# DSPPower.net
KiCad netlist of a schematic drawn in Altium Designer
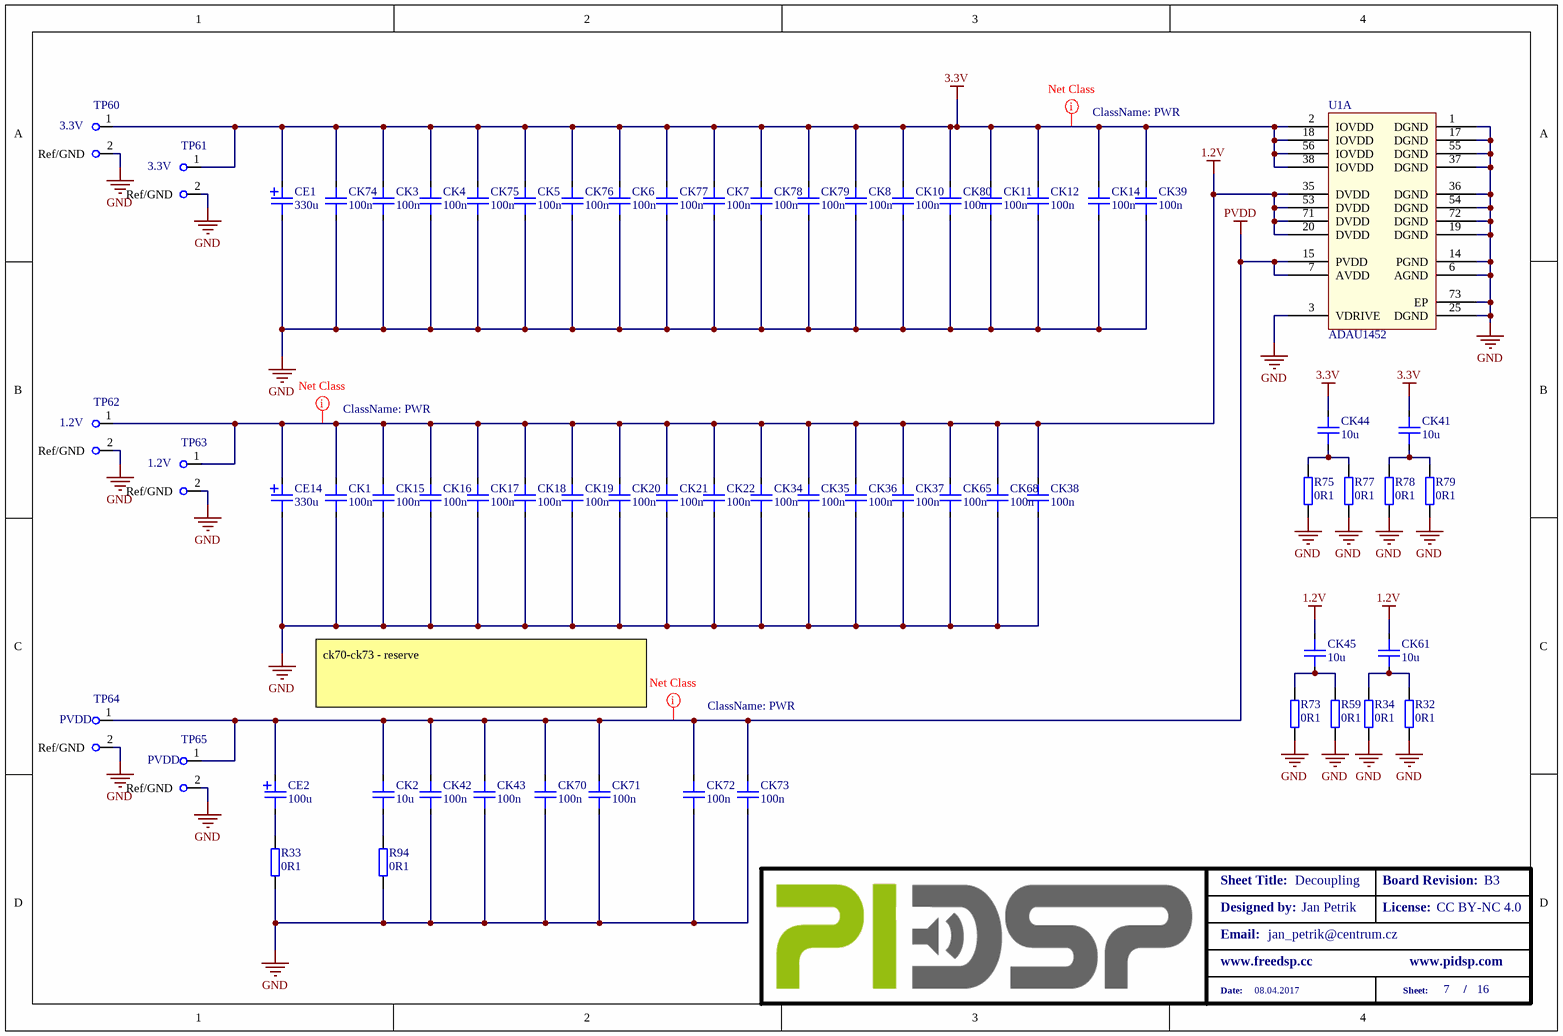
[diagram p0: DSPPower.SchDoc]

(export (version "E")
  (design (tool "Eeschema 10.0.6"))
  (components
    (comp (ref "CE1")
      (value "330u")
      (footprint "CAPAE6.8X6.8(D_SIZE)")
      (description "Polymer Aluminium Solid Capacitor 330uF, 6.3V")
      (fields
        (field (name "VOLTAGE") "6.3V")
        (field (name "TOLERANCE") "20%/35V")
        (field (name "AUTHOR") "JP/27.03.2014")
      )
      (libsource (lib "JP_C") (part "330u-6.3V-B6-OSCON"))
    )
    (comp (ref "CE2")
      (value "100u")
      (footprint "CAPAE6.8X6.8(D_SIZE)")
      (description "Polymer Aluminium Solid Capacitor 100uF, 16V")
      (fields
        (field (name "TOLERANCE") "20%/16V")
        (field (name "VOLTAGE") "16V")
        (field (name "AUTHOR") "JP/27.03.2014")
      )
      (libsource (lib "JP_C") (part "100u-16V-B6-OSCON"))
    )
    (comp (ref "CE14")
      (value "330u")
      (footprint "CAPAE6.8X6.8(D_SIZE)")
      (description "Polymer Aluminium Solid Capacitor 330uF, 6.3V")
      (fields
        (field (name "VOLTAGE") "6.3V")
        (field (name "TOLERANCE") "20%/35V")
        (field (name "AUTHOR") "JP/27.03.2014")
      )
      (libsource (lib "JP_C") (part "330u-6.3V-B6-OSCON"))
    )
    (comp (ref "CK1")
      (value "100n")
      (footprint "CAPC1608X09N(SMC0603)")
      (description "MLCC")
      (fields
        (field (name "TOLERANCE") "10%")
        (field (name "VOLTAGE") "50V")
        (field (name "AUTHOR") "JP/27.03.2014")
      )
      (libsource (lib "JP_C") (part "100n-50V-0603-X7R"))
    )
    (comp (ref "CK2")
      (value "10u")
      (footprint "CAPC3216X12N(SMC1206)")
      (description "MLCC")
      (fields
        (field (name "TOLERANCE") "10%")
        (field (name "VOLTAGE") "50")
        (field (name "AUTHOR") "JP/10.06.2014")
      )
      (libsource (lib "JP_C") (part "10u-50V-1206-X5R"))
    )
    (comp (ref "CK3")
      (value "100n")
      (footprint "CAPC1608X09N(SMC0603)_Fanout")
      (description "MLCC")
      (fields
        (field (name "TOLERANCE") "10%")
        (field (name "VOLTAGE") "50V")
        (field (name "AUTHOR") "JP/27.03.2014")
      )
      (libsource (lib "JP_C") (part "100n-50V-0603-X7R"))
    )
    (comp (ref "CK4")
      (value "100n")
      (footprint "CAPC1608X09N(SMC0603)_Fanout")
      (description "MLCC")
      (fields
        (field (name "TOLERANCE") "10%")
        (field (name "VOLTAGE") "50V")
        (field (name "AUTHOR") "JP/27.03.2014")
      )
      (libsource (lib "JP_C") (part "100n-50V-0603-X7R"))
    )
    (comp (ref "CK5")
      (value "100n")
      (footprint "CAPC1608X09N(SMC0603)_Fanout")
      (description "MLCC")
      (fields
        (field (name "VOLTAGE") "50V")
        (field (name "TOLERANCE") "10%")
        (field (name "AUTHOR") "JP/27.03.2014")
      )
      (libsource (lib "JP_C") (part "100n-50V-0603-X7R"))
    )
    (comp (ref "CK6")
      (value "100n")
      (footprint "CAPC1608X09N(SMC0603)_Fanout")
      (description "MLCC")
      (fields
        (field (name "VOLTAGE") "50V")
        (field (name "TOLERANCE") "10%")
        (field (name "AUTHOR") "JP/27.03.2014")
      )
      (libsource (lib "JP_C") (part "100n-50V-0603-X7R"))
    )
    (comp (ref "CK7")
      (value "100n")
      (footprint "CAPC1608X09N(SMC0603)_Fanout")
      (description "MLCC")
      (fields
        (field (name "VOLTAGE") "50V")
        (field (name "TOLERANCE") "10%")
        (field (name "AUTHOR") "JP/27.03.2014")
      )
      (libsource (lib "JP_C") (part "100n-50V-0603-X7R"))
    )
    (comp (ref "CK8")
      (value "100n")
      (footprint "CAPC1608X09N(SMC0603)_Fanout")
      (description "MLCC")
      (fields
        (field (name "VOLTAGE") "50V")
        (field (name "TOLERANCE") "10%")
        (field (name "AUTHOR") "JP/27.03.2014")
      )
      (libsource (lib "JP_C") (part "100n-50V-0603-X7R"))
    )
    (comp (ref "CK10")
      (value "100n")
      (footprint "CAPC1608X09N(SMC0603)_Fanout")
      (description "MLCC")
      (fields
        (field (name "VOLTAGE") "50V")
        (field (name "TOLERANCE") "10%")
        (field (name "AUTHOR") "JP/27.03.2014")
      )
      (libsource (lib "JP_C") (part "100n-50V-0603-X7R"))
    )
    (comp (ref "CK11")
      (value "100n")
      (footprint "CAPC1608X09N(SMC0603)")
      (description "MLCC")
      (fields
        (field (name "VOLTAGE") "50V")
        (field (name "TOLERANCE") "10%")
        (field (name "AUTHOR") "JP/27.03.2014")
      )
      (libsource (lib "JP_C") (part "100n-50V-0603-X7R"))
    )
    (comp (ref "CK12")
      (value "100n")
      (footprint "CAPC1608X09N(SMC0603)")
      (description "MLCC")
      (fields
        (field (name "VOLTAGE") "50V")
        (field (name "TOLERANCE") "10%")
        (field (name "AUTHOR") "JP/27.03.2014")
      )
      (libsource (lib "JP_C") (part "100n-50V-0603-X7R"))
    )
    (comp (ref "CK14")
      (value "100n")
      (footprint "CAPC1608X09N(SMC0603)")
      (description "MLCC")
      (fields
        (field (name "VOLTAGE") "50V")
        (field (name "TOLERANCE") "10%")
        (field (name "AUTHOR") "JP/27.03.2014")
      )
      (libsource (lib "JP_C") (part "100n-50V-0603-X7R"))
    )
    (comp (ref "CK15")
      (value "100n")
      (footprint "CAPC1608X09N(SMC0603)")
      (description "MLCC")
      (fields
        (field (name "TOLERANCE") "10%")
        (field (name "VOLTAGE") "50V")
        (field (name "AUTHOR") "JP/27.03.2014")
      )
      (libsource (lib "JP_C") (part "100n-50V-0603-X7R"))
    )
    (comp (ref "CK16")
      (value "100n")
      (footprint "CAPC1608X09N(SMC0603)")
      (description "MLCC")
      (fields
        (field (name "TOLERANCE") "10%")
        (field (name "VOLTAGE") "50V")
        (field (name "AUTHOR") "JP/27.03.2014")
      )
      (libsource (lib "JP_C") (part "100n-50V-0603-X7R"))
    )
    (comp (ref "CK17")
      (value "100n")
      (footprint "CAPC1608X09N(SMC0603)")
      (description "MLCC")
      (fields
        (field (name "VOLTAGE") "50V")
        (field (name "TOLERANCE") "10%")
        (field (name "AUTHOR") "JP/27.03.2014")
      )
      (libsource (lib "JP_C") (part "100n-50V-0603-X7R"))
    )
    (comp (ref "CK18")
      (value "100n")
      (footprint "CAPC1608X09N(SMC0603)")
      (description "MLCC")
      (fields
        (field (name "VOLTAGE") "50V")
        (field (name "TOLERANCE") "10%")
        (field (name "AUTHOR") "JP/27.03.2014")
      )
      (libsource (lib "JP_C") (part "100n-50V-0603-X7R"))
    )
    (comp (ref "CK19")
      (value "100n")
      (footprint "CAPC1608X09N(SMC0603)")
      (description "MLCC")
      (fields
        (field (name "VOLTAGE") "50V")
        (field (name "TOLERANCE") "10%")
        (field (name "AUTHOR") "JP/27.03.2014")
      )
      (libsource (lib "JP_C") (part "100n-50V-0603-X7R"))
    )
    (comp (ref "CK20")
      (value "100n")
      (footprint "CAPC1608X09N(SMC0603)")
      (description "MLCC")
      (fields
        (field (name "VOLTAGE") "50V")
        (field (name "TOLERANCE") "10%")
        (field (name "AUTHOR") "JP/27.03.2014")
      )
      (libsource (lib "JP_C") (part "100n-50V-0603-X7R"))
    )
    (comp (ref "CK21")
      (value "100n")
      (footprint "CAPC1608X09N(SMC0603)")
      (description "MLCC")
      (fields
        (field (name "VOLTAGE") "50V")
        (field (name "TOLERANCE") "10%")
        (field (name "AUTHOR") "JP/27.03.2014")
      )
      (libsource (lib "JP_C") (part "100n-50V-0603-X7R"))
    )
    (comp (ref "CK22")
      (value "100n")
      (footprint "CAPC1608X09N(SMC0603)")
      (description "MLCC")
      (fields
        (field (name "TOLERANCE") "10%")
        (field (name "VOLTAGE") "50V")
        (field (name "AUTHOR") "JP/27.03.2014")
      )
      (libsource (lib "JP_C") (part "100n-50V-0603-X7R"))
    )
    (comp (ref "CK34")
      (value "100n")
      (footprint "CAPC1608X09N(SMC0603)")
      (description "MLCC")
      (fields
        (field (name "TOLERANCE") "10%")
        (field (name "VOLTAGE") "50V")
        (field (name "AUTHOR") "JP/27.03.2014")
      )
      (libsource (lib "JP_C") (part "100n-50V-0603-X7R"))
    )
    (comp (ref "CK35")
      (value "100n")
      (footprint "CAPC1608X09N(SMC0603)")
      (description "MLCC")
      (fields
        (field (name "TOLERANCE") "10%")
        (field (name "VOLTAGE") "50V")
        (field (name "AUTHOR") "JP/27.03.2014")
      )
      (libsource (lib "JP_C") (part "100n-50V-0603-X7R"))
    )
    (comp (ref "CK36")
      (value "100n")
      (footprint "CAPC1608X09N(SMC0603)")
      (description "MLCC")
      (fields
        (field (name "TOLERANCE") "10%")
        (field (name "VOLTAGE") "50V")
        (field (name "AUTHOR") "JP/27.03.2014")
      )
      (libsource (lib "JP_C") (part "100n-50V-0603-X7R"))
    )
    (comp (ref "CK37")
      (value "100n")
      (footprint "CAPC1608X09N(SMC0603)")
      (description "MLCC")
      (fields
        (field (name "TOLERANCE") "10%")
        (field (name "VOLTAGE") "50V")
        (field (name "AUTHOR") "JP/27.03.2014")
      )
      (libsource (lib "JP_C") (part "100n-50V-0603-X7R"))
    )
    (comp (ref "CK38")
      (value "100n")
      (footprint "CAPC1608X09N(SMC0603)")
      (description "MLCC")
      (fields
        (field (name "TOLERANCE") "10%")
        (field (name "VOLTAGE") "50V")
        (field (name "AUTHOR") "JP/27.03.2014")
      )
      (libsource (lib "JP_C") (part "100n-50V-0603-X7R"))
    )
    (comp (ref "CK39")
      (value "100n")
      (footprint "CAPC1608X09N(SMC0603)")
      (description "MLCC")
      (fields
        (field (name "VOLTAGE") "50V")
        (field (name "TOLERANCE") "10%")
        (field (name "AUTHOR") "JP/27.03.2014")
      )
      (libsource (lib "JP_C") (part "100n-50V-0603-X7R"))
    )
    (comp (ref "CK41")
      (value "10u")
      (footprint "CAPC3216X12N(SMC1206)")
      (description "MLCC")
      (fields
        (field (name "TOLERANCE") "10%")
        (field (name "VOLTAGE") "50")
        (field (name "AUTHOR") "JP/10.06.2014")
      )
      (libsource (lib "JP_C") (part "10u-50V-1206-X5R"))
    )
    (comp (ref "CK42")
      (value "100n")
      (footprint "CAPC1608X09N(SMC0603)")
      (description "MLCC")
      (fields
        (field (name "TOLERANCE") "10%")
        (field (name "VOLTAGE") "50V")
        (field (name "AUTHOR") "JP/27.03.2014")
      )
      (libsource (lib "JP_C") (part "100n-50V-0603-X7R"))
    )
    (comp (ref "CK43")
      (value "100n")
      (footprint "CAPC1608X09N(SMC0603)")
      (description "MLCC")
      (fields
        (field (name "VOLTAGE") "50V")
        (field (name "TOLERANCE") "10%")
        (field (name "AUTHOR") "JP/27.03.2014")
      )
      (libsource (lib "JP_C") (part "100n-50V-0603-X7R"))
    )
    (comp (ref "CK44")
      (value "10u")
      (footprint "CAPC3216X12N(SMC1206)")
      (description "MLCC")
      (fields
        (field (name "TOLERANCE") "10%")
        (field (name "VOLTAGE") "50")
        (field (name "AUTHOR") "JP/10.06.2014")
      )
      (libsource (lib "JP_C") (part "10u-50V-1206-X5R"))
    )
    (comp (ref "CK45")
      (value "10u")
      (footprint "CAPC3216X12N(SMC1206)")
      (description "MLCC")
      (fields
        (field (name "TOLERANCE") "10%")
        (field (name "VOLTAGE") "50")
        (field (name "AUTHOR") "JP/10.06.2014")
      )
      (libsource (lib "JP_C") (part "10u-50V-1206-X5R"))
    )
    (comp (ref "CK61")
      (value "10u")
      (footprint "CAPC3216X12N(SMC1206)")
      (description "MLCC")
      (fields
        (field (name "TOLERANCE") "10%")
        (field (name "VOLTAGE") "50")
        (field (name "AUTHOR") "JP/10.06.2014")
      )
      (libsource (lib "JP_C") (part "10u-50V-1206-X5R"))
    )
    (comp (ref "CK65")
      (value "100n")
      (footprint "CAPC1608X09N(SMC0603)")
      (description "MLCC")
      (fields
        (field (name "TOLERANCE") "10%")
        (field (name "VOLTAGE") "50V")
        (field (name "AUTHOR") "JP/27.03.2014")
      )
      (libsource (lib "JP_C") (part "100n-50V-0603-X7R"))
    )
    (comp (ref "CK68")
      (value "100n")
      (footprint "CAPC1608X09N(SMC0603)")
      (description "MLCC")
      (fields
        (field (name "TOLERANCE") "10%")
        (field (name "VOLTAGE") "50V")
        (field (name "AUTHOR") "JP/27.03.2014")
      )
      (libsource (lib "JP_C") (part "100n-50V-0603-X7R"))
    )
    (comp (ref "CK70")
      (value "100n")
      (footprint "CAPC1608X09N(SMC0603)")
      (description "MLCC")
      (fields
        (field (name "VOLTAGE") "50V")
        (field (name "TOLERANCE") "10%")
        (field (name "AUTHOR") "JP/27.03.2014")
      )
      (libsource (lib "JP_C") (part "100n-50V-0603-X7R"))
    )
    (comp (ref "CK71")
      (value "100n")
      (footprint "CAPC1608X09N(SMC0603)")
      (description "MLCC")
      (fields
        (field (name "VOLTAGE") "50V")
        (field (name "TOLERANCE") "10%")
        (field (name "AUTHOR") "JP/27.03.2014")
      )
      (libsource (lib "JP_C") (part "100n-50V-0603-X7R"))
    )
    (comp (ref "CK72")
      (value "100n")
      (footprint "CAPC1608X09N(SMC0603)")
      (description "MLCC")
      (fields
        (field (name "VOLTAGE") "50V")
        (field (name "TOLERANCE") "10%")
        (field (name "AUTHOR") "JP/27.03.2014")
      )
      (libsource (lib "JP_C") (part "100n-50V-0603-X7R"))
    )
    (comp (ref "CK73")
      (value "100n")
      (footprint "CAPC1608X09N(SMC0603)")
      (description "MLCC")
      (fields
        (field (name "VOLTAGE") "50V")
        (field (name "TOLERANCE") "10%")
        (field (name "AUTHOR") "JP/27.03.2014")
      )
      (libsource (lib "JP_C") (part "100n-50V-0603-X7R"))
    )
    (comp (ref "CK74")
      (value "100n")
      (footprint "CAPC1608X09N(SMC0603)_Fanout")
      (description "MLCC")
      (fields
        (field (name "VOLTAGE") "50V")
        (field (name "TOLERANCE") "10%")
        (field (name "AUTHOR") "JP/27.03.2014")
      )
      (libsource (lib "JP_C") (part "100n-50V-0603-X7R"))
    )
    (comp (ref "CK75")
      (value "100n")
      (footprint "CAPC1608X09N(SMC0603)_Fanout")
      (description "MLCC")
      (fields
        (field (name "VOLTAGE") "50V")
        (field (name "TOLERANCE") "10%")
        (field (name "AUTHOR") "JP/27.03.2014")
      )
      (libsource (lib "JP_C") (part "100n-50V-0603-X7R"))
    )
    (comp (ref "CK76")
      (value "100n")
      (footprint "CAPC1608X09N(SMC0603)_Fanout")
      (description "MLCC")
      (fields
        (field (name "VOLTAGE") "50V")
        (field (name "TOLERANCE") "10%")
        (field (name "AUTHOR") "JP/27.03.2014")
      )
      (libsource (lib "JP_C") (part "100n-50V-0603-X7R"))
    )
    (comp (ref "CK77")
      (value "100n")
      (footprint "CAPC1608X09N(SMC0603)_Fanout")
      (description "MLCC")
      (fields
        (field (name "VOLTAGE") "50V")
        (field (name "TOLERANCE") "10%")
        (field (name "AUTHOR") "JP/27.03.2014")
      )
      (libsource (lib "JP_C") (part "100n-50V-0603-X7R"))
    )
    (comp (ref "CK78")
      (value "100n")
      (footprint "CAPC1608X09N(SMC0603)_Fanout")
      (description "MLCC")
      (fields
        (field (name "VOLTAGE") "50V")
        (field (name "TOLERANCE") "10%")
        (field (name "AUTHOR") "JP/27.03.2014")
      )
      (libsource (lib "JP_C") (part "100n-50V-0603-X7R"))
    )
    (comp (ref "CK79")
      (value "100n")
      (footprint "CAPC1608X09N(SMC0603)_Fanout")
      (description "MLCC")
      (fields
        (field (name "VOLTAGE") "50V")
        (field (name "TOLERANCE") "10%")
        (field (name "AUTHOR") "JP/27.03.2014")
      )
      (libsource (lib "JP_C") (part "100n-50V-0603-X7R"))
    )
    (comp (ref "CK80")
      (value "100n")
      (footprint "CAPC1608X09N(SMC0603)_Fanout")
      (description "MLCC")
      (fields
        (field (name "VOLTAGE") "50V")
        (field (name "TOLERANCE") "10%")
        (field (name "AUTHOR") "JP/27.03.2014")
      )
      (libsource (lib "JP_C") (part "100n-50V-0603-X7R"))
    )
    (comp (ref "R32")
      (value "0R1")
      (footprint "RESC1608X06N(SMR0603)")
      (description "Chip Resistor")
      (fields (field (name "AUTHOR") "JP/10.06.2014"))
      (libsource (lib "JP_R") (part "0R1-100mW-0603-ThickFilm"))
    )
    (comp (ref "R33")
      (value "0R1")
      (footprint "RESC1608X06N(SMR0603)")
      (description "Chip Resistor")
      (fields (field (name "AUTHOR") "JP/10.06.2014"))
      (libsource (lib "JP_R") (part "0R1-100mW-0603-ThickFilm"))
    )
    (comp (ref "R34")
      (value "0R1")
      (footprint "RESC1608X06N(SMR0603)")
      (description "Chip Resistor")
      (fields (field (name "AUTHOR") "JP/10.06.2014"))
      (libsource (lib "JP_R") (part "0R1-100mW-0603-ThickFilm"))
    )
    (comp (ref "R59")
      (value "0R1")
      (footprint "RESC1608X06N(SMR0603)")
      (description "Chip Resistor")
      (fields (field (name "AUTHOR") "JP/10.06.2014"))
      (libsource (lib "JP_R") (part "0R1-100mW-0603-ThickFilm"))
    )
    (comp (ref "R73")
      (value "0R1")
      (footprint "RESC1608X06N(SMR0603)")
      (description "Chip Resistor")
      (fields (field (name "AUTHOR") "JP/10.06.2014"))
      (libsource (lib "JP_R") (part "0R1-100mW-0603-ThickFilm"))
    )
    (comp (ref "R75")
      (value "0R1")
      (footprint "RESC1608X06N(SMR0603)")
      (description "Chip Resistor")
      (fields (field (name "AUTHOR") "JP/10.06.2014"))
      (libsource (lib "JP_R") (part "0R1-100mW-0603-ThickFilm"))
    )
    (comp (ref "R77")
      (value "0R1")
      (footprint "RESC1608X06N(SMR0603)")
      (description "Chip Resistor")
      (fields (field (name "AUTHOR") "JP/10.06.2014"))
      (libsource (lib "JP_R") (part "0R1-100mW-0603-ThickFilm"))
    )
    (comp (ref "R78")
      (value "0R1")
      (footprint "RESC1608X06N(SMR0603)")
      (description "Chip Resistor")
      (fields (field (name "AUTHOR") "JP/10.06.2014"))
      (libsource (lib "JP_R") (part "0R1-100mW-0603-ThickFilm"))
    )
    (comp (ref "R79")
      (value "0R1")
      (footprint "RESC1608X06N(SMR0603)")
      (description "Chip Resistor")
      (fields (field (name "AUTHOR") "JP/10.06.2014"))
      (libsource (lib "JP_R") (part "0R1-100mW-0603-ThickFilm"))
    )
    (comp (ref "R94")
      (value "0R1")
      (footprint "RESC1608X06N(SMR0603)")
      (description "Chip Resistor")
      (fields (field (name "AUTHOR") "JP/10.06.2014"))
      (libsource (lib "JP_R") (part "0R1-100mW-0603-ThickFilm"))
    )
    (comp (ref "TP60")
      (value "3.3V")
      (footprint "JP_Misc:HS/PDN_Testpoint")
      (description "Testpoint - HS/PDN")
      (libsource (lib "JP_Misc") (part "TEST_POINT_HS/PDN"))
    )
    (comp (ref "TP61")
      (value "3.3V")
      (footprint "JP_Misc:HS/PDN_Testpoint")
      (description "Testpoint - HS/PDN")
      (libsource (lib "JP_Misc") (part "TEST_POINT_HS/PDN"))
    )
    (comp (ref "TP62")
      (value "1.2V")
      (footprint "JP_Misc:HS/PDN_Testpoint")
      (description "Testpoint - HS/PDN")
      (libsource (lib "JP_Misc") (part "TEST_POINT_HS/PDN"))
    )
    (comp (ref "TP63")
      (value "1.2V")
      (footprint "JP_Misc:HS/PDN_Testpoint")
      (description "Testpoint - HS/PDN")
      (libsource (lib "JP_Misc") (part "TEST_POINT_HS/PDN"))
    )
    (comp (ref "TP64")
      (value "PVDD")
      (footprint "JP_Misc:HS/PDN_Testpoint")
      (description "Testpoint - HS/PDN")
      (libsource (lib "JP_Misc") (part "TEST_POINT_HS/PDN"))
    )
    (comp (ref "TP65")
      (value "PVDD")
      (footprint "JP_Misc:HS/PDN_Testpoint")
      (description "Testpoint - HS/PDN")
      (libsource (lib "JP_Misc") (part "TEST_POINT_HS/PDN"))
    )
    (comp (ref "U1")
      (value "ADAU1452")
      (footprint "CP_72_6-handsoldering")
      (libsource (lib "JP_IC") (part "ADAU1452"))
    )
  )
  (nets
    (net (code "1") (name "1.2V") (class "Default")
      (node (ref "CE14") (pin "1") (pinfunction "1_1") (pintype "passive"))
      (node (ref "CK1") (pin "1") (pinfunction "1_1") (pintype "passive"))
      (node (ref "CK15") (pin "1") (pinfunction "1_1") (pintype "passive"))
      (node (ref "CK16") (pin "1") (pinfunction "1_1") (pintype "passive"))
      (node (ref "CK17") (pin "1") (pinfunction "1_1") (pintype "passive"))
      (node (ref "CK18") (pin "1") (pinfunction "1_1") (pintype "passive"))
      (node (ref "CK19") (pin "1") (pinfunction "1_1") (pintype "passive"))
      (node (ref "CK20") (pin "1") (pinfunction "1_1") (pintype "passive"))
      (node (ref "CK21") (pin "1") (pinfunction "1_1") (pintype "passive"))
      (node (ref "CK22") (pin "1") (pinfunction "1_1") (pintype "passive"))
      (node (ref "CK34") (pin "1") (pinfunction "1_1") (pintype "passive"))
      (node (ref "CK35") (pin "1") (pinfunction "1_1") (pintype "passive"))
      (node (ref "CK36") (pin "1") (pinfunction "1_1") (pintype "passive"))
      (node (ref "CK37") (pin "1") (pinfunction "1_1") (pintype "passive"))
      (node (ref "CK38") (pin "1") (pinfunction "1_1") (pintype "passive"))
      (node (ref "CK45") (pin "1") (pinfunction "1_1") (pintype "passive"))
      (node (ref "CK61") (pin "1") (pinfunction "1_1") (pintype "passive"))
      (node (ref "CK65") (pin "1") (pinfunction "1_1") (pintype "passive"))
      (node (ref "CK68") (pin "1") (pinfunction "1_1") (pintype "passive"))
      (node (ref "TP62") (pin "1") (pintype "passive"))
      (node (ref "TP63") (pin "1") (pintype "passive"))
      (node (ref "U1") (pin "20") (pinfunction "DVDD_20") (pintype "power_in"))
      (node (ref "U1") (pin "35") (pinfunction "DVDD_35") (pintype "power_in"))
      (node (ref "U1") (pin "53") (pinfunction "DVDD_53") (pintype "power_in"))
      (node (ref "U1") (pin "71") (pinfunction "DVDD_71") (pintype "power_in"))
    )
    (net (code "2") (name "3.3V") (class "Default")
      (node (ref "CE1") (pin "1") (pinfunction "1_1") (pintype "passive"))
      (node (ref "CK10") (pin "1") (pinfunction "1_1") (pintype "passive"))
      (node (ref "CK11") (pin "1") (pinfunction "1_1") (pintype "passive"))
      (node (ref "CK12") (pin "1") (pinfunction "1_1") (pintype "passive"))
      (node (ref "CK14") (pin "1") (pinfunction "1_1") (pintype "passive"))
      (node (ref "CK3") (pin "1") (pinfunction "1_1") (pintype "passive"))
      (node (ref "CK39") (pin "1") (pinfunction "1_1") (pintype "passive"))
      (node (ref "CK4") (pin "1") (pinfunction "1_1") (pintype "passive"))
      (node (ref "CK41") (pin "1") (pinfunction "1_1") (pintype "passive"))
      (node (ref "CK44") (pin "1") (pinfunction "1_1") (pintype "passive"))
      (node (ref "CK5") (pin "1") (pinfunction "1_1") (pintype "passive"))
      (node (ref "CK6") (pin "1") (pinfunction "1_1") (pintype "passive"))
      (node (ref "CK7") (pin "1") (pinfunction "1_1") (pintype "passive"))
      (node (ref "CK74") (pin "1") (pinfunction "1_1") (pintype "passive"))
      (node (ref "CK75") (pin "1") (pinfunction "1_1") (pintype "passive"))
      (node (ref "CK76") (pin "1") (pinfunction "1_1") (pintype "passive"))
      (node (ref "CK77") (pin "1") (pinfunction "1_1") (pintype "passive"))
      (node (ref "CK78") (pin "1") (pinfunction "1_1") (pintype "passive"))
      (node (ref "CK79") (pin "1") (pinfunction "1_1") (pintype "passive"))
      (node (ref "CK8") (pin "1") (pinfunction "1_1") (pintype "passive"))
      (node (ref "CK80") (pin "1") (pinfunction "1_1") (pintype "passive"))
      (node (ref "TP60") (pin "1") (pintype "passive"))
      (node (ref "TP61") (pin "1") (pintype "passive"))
      (node (ref "U1") (pin "18") (pinfunction "IOVDD_18") (pintype "power_in"))
      (node (ref "U1") (pin "2") (pinfunction "IOVDD_2") (pintype "power_in"))
      (node (ref "U1") (pin "38") (pinfunction "IOVDD_38") (pintype "power_in"))
      (node (ref "U1") (pin "56") (pinfunction "IOVDD_56") (pintype "power_in"))
    )
    (net (code "3") (name "GND") (class "Default")
      (node (ref "CE1") (pin "2") (pinfunction "2_2") (pintype "passive"))
      (node (ref "CE14") (pin "2") (pinfunction "2_2") (pintype "passive"))
      (node (ref "CK1") (pin "2") (pinfunction "2_2") (pintype "passive"))
      (node (ref "CK10") (pin "2") (pinfunction "2_2") (pintype "passive"))
      (node (ref "CK11") (pin "2") (pinfunction "2_2") (pintype "passive"))
      (node (ref "CK12") (pin "2") (pinfunction "2_2") (pintype "passive"))
      (node (ref "CK14") (pin "2") (pinfunction "2_2") (pintype "passive"))
      (node (ref "CK15") (pin "2") (pinfunction "2_2") (pintype "passive"))
      (node (ref "CK16") (pin "2") (pinfunction "2_2") (pintype "passive"))
      (node (ref "CK17") (pin "2") (pinfunction "2_2") (pintype "passive"))
      (node (ref "CK18") (pin "2") (pinfunction "2_2") (pintype "passive"))
      (node (ref "CK19") (pin "2") (pinfunction "2_2") (pintype "passive"))
      (node (ref "CK20") (pin "2") (pinfunction "2_2") (pintype "passive"))
      (node (ref "CK21") (pin "2") (pinfunction "2_2") (pintype "passive"))
      (node (ref "CK22") (pin "2") (pinfunction "2_2") (pintype "passive"))
      (node (ref "CK3") (pin "2") (pinfunction "2_2") (pintype "passive"))
      (node (ref "CK34") (pin "2") (pinfunction "2_2") (pintype "passive"))
      (node (ref "CK35") (pin "2") (pinfunction "2_2") (pintype "passive"))
      (node (ref "CK36") (pin "2") (pinfunction "2_2") (pintype "passive"))
      (node (ref "CK37") (pin "2") (pinfunction "2_2") (pintype "passive"))
      (node (ref "CK38") (pin "2") (pinfunction "2_2") (pintype "passive"))
      (node (ref "CK39") (pin "2") (pinfunction "2_2") (pintype "passive"))
      (node (ref "CK4") (pin "2") (pinfunction "2_2") (pintype "passive"))
      (node (ref "CK42") (pin "2") (pinfunction "2_2") (pintype "passive"))
      (node (ref "CK43") (pin "2") (pinfunction "2_2") (pintype "passive"))
      (node (ref "CK5") (pin "2") (pinfunction "2_2") (pintype "passive"))
      (node (ref "CK6") (pin "2") (pinfunction "2_2") (pintype "passive"))
      (node (ref "CK65") (pin "2") (pinfunction "2_2") (pintype "passive"))
      (node (ref "CK68") (pin "2") (pinfunction "2_2") (pintype "passive"))
      (node (ref "CK7") (pin "2") (pinfunction "2_2") (pintype "passive"))
      (node (ref "CK70") (pin "2") (pinfunction "2_2") (pintype "passive"))
      (node (ref "CK71") (pin "2") (pinfunction "2_2") (pintype "passive"))
      (node (ref "CK72") (pin "2") (pinfunction "2_2") (pintype "passive"))
      (node (ref "CK73") (pin "2") (pinfunction "2_2") (pintype "passive"))
      (node (ref "CK74") (pin "2") (pinfunction "2_2") (pintype "passive"))
      (node (ref "CK75") (pin "2") (pinfunction "2_2") (pintype "passive"))
      (node (ref "CK76") (pin "2") (pinfunction "2_2") (pintype "passive"))
      (node (ref "CK77") (pin "2") (pinfunction "2_2") (pintype "passive"))
      (node (ref "CK78") (pin "2") (pinfunction "2_2") (pintype "passive"))
      (node (ref "CK79") (pin "2") (pinfunction "2_2") (pintype "passive"))
      (node (ref "CK8") (pin "2") (pinfunction "2_2") (pintype "passive"))
      (node (ref "CK80") (pin "2") (pinfunction "2_2") (pintype "passive"))
      (node (ref "R32") (pin "2") (pinfunction "2_2") (pintype "passive"))
      (node (ref "R33") (pin "2") (pinfunction "2_2") (pintype "passive"))
      (node (ref "R34") (pin "2") (pinfunction "2_2") (pintype "passive"))
      (node (ref "R59") (pin "2") (pinfunction "2_2") (pintype "passive"))
      (node (ref "R73") (pin "2") (pinfunction "2_2") (pintype "passive"))
      (node (ref "R75") (pin "2") (pinfunction "2_2") (pintype "passive"))
      (node (ref "R77") (pin "2") (pinfunction "2_2") (pintype "passive"))
      (node (ref "R78") (pin "2") (pinfunction "2_2") (pintype "passive"))
      (node (ref "R79") (pin "2") (pinfunction "2_2") (pintype "passive"))
      (node (ref "R94") (pin "2") (pinfunction "2_2") (pintype "passive"))
      (node (ref "TP60") (pin "2") (pinfunction "Ref/GND_2") (pintype "passive"))
      (node (ref "TP61") (pin "2") (pinfunction "Ref/GND_2") (pintype "passive"))
      (node (ref "TP62") (pin "2") (pinfunction "Ref/GND_2") (pintype "passive"))
      (node (ref "TP63") (pin "2") (pinfunction "Ref/GND_2") (pintype "passive"))
      (node (ref "TP64") (pin "2") (pinfunction "Ref/GND_2") (pintype "passive"))
      (node (ref "TP65") (pin "2") (pinfunction "Ref/GND_2") (pintype "passive"))
      (node (ref "U1") (pin "1") (pinfunction "DGND_1") (pintype "power_in"))
      (node (ref "U1") (pin "14") (pinfunction "PGND_14") (pintype "power_in"))
      (node (ref "U1") (pin "17") (pinfunction "DGND_17") (pintype "power_in"))
      (node (ref "U1") (pin "19") (pinfunction "DGND_19") (pintype "power_in"))
      (node (ref "U1") (pin "25") (pinfunction "DGND_25") (pintype "power_in"))
      (node (ref "U1") (pin "3") (pinfunction "VDRIVE_3") (pintype "power_in"))
      (node (ref "U1") (pin "36") (pinfunction "DGND_36") (pintype "power_in"))
      (node (ref "U1") (pin "37") (pinfunction "DGND_37") (pintype "power_in"))
      (node (ref "U1") (pin "54") (pinfunction "DGND_54") (pintype "power_in"))
      (node (ref "U1") (pin "55") (pinfunction "DGND_55") (pintype "power_in"))
      (node (ref "U1") (pin "6") (pinfunction "AGND_6") (pintype "power_in"))
      (node (ref "U1") (pin "72") (pinfunction "DGND_72") (pintype "power_in"))
      (node (ref "U1") (pin "73") (pinfunction "EP_73") (pintype "power_in"))
    )
    (net (code "4") (name "Net-(CE2-Pad2)") (class "Default")
      (node (ref "CE2") (pin "2") (pinfunction "2_2") (pintype "passive"))
      (node (ref "R33") (pin "1") (pinfunction "1_1") (pintype "passive"))
    )
    (net (code "5") (name "Net-(CK2-Pad2)") (class "Default")
      (node (ref "CK2") (pin "2") (pinfunction "2_2") (pintype "passive"))
      (node (ref "R94") (pin "1") (pinfunction "1_1") (pintype "passive"))
    )
    (net (code "6") (name "Net-(CK41-Pad2)") (class "Default")
      (node (ref "CK41") (pin "2") (pinfunction "2_2") (pintype "passive"))
      (node (ref "R78") (pin "1") (pinfunction "1_1") (pintype "passive"))
      (node (ref "R79") (pin "1") (pinfunction "1_1") (pintype "passive"))
    )
    (net (code "7") (name "Net-(CK44-Pad2)") (class "Default")
      (node (ref "CK44") (pin "2") (pinfunction "2_2") (pintype "passive"))
      (node (ref "R75") (pin "1") (pinfunction "1_1") (pintype "passive"))
      (node (ref "R77") (pin "1") (pinfunction "1_1") (pintype "passive"))
    )
    (net (code "8") (name "Net-(CK45-Pad2)") (class "Default")
      (node (ref "CK45") (pin "2") (pinfunction "2_2") (pintype "passive"))
      (node (ref "R59") (pin "1") (pinfunction "1_1") (pintype "passive"))
      (node (ref "R73") (pin "1") (pinfunction "1_1") (pintype "passive"))
    )
    (net (code "9") (name "Net-(CK61-Pad2)") (class "Default")
      (node (ref "CK61") (pin "2") (pinfunction "2_2") (pintype "passive"))
      (node (ref "R32") (pin "1") (pinfunction "1_1") (pintype "passive"))
      (node (ref "R34") (pin "1") (pinfunction "1_1") (pintype "passive"))
    )
    (net (code "10") (name "PVDD") (class "Default")
      (node (ref "CE2") (pin "1") (pinfunction "1_1") (pintype "passive"))
      (node (ref "CK2") (pin "1") (pinfunction "1_1") (pintype "passive"))
      (node (ref "CK42") (pin "1") (pinfunction "1_1") (pintype "passive"))
      (node (ref "CK43") (pin "1") (pinfunction "1_1") (pintype "passive"))
      (node (ref "CK70") (pin "1") (pinfunction "1_1") (pintype "passive"))
      (node (ref "CK71") (pin "1") (pinfunction "1_1") (pintype "passive"))
      (node (ref "CK72") (pin "1") (pinfunction "1_1") (pintype "passive"))
      (node (ref "CK73") (pin "1") (pinfunction "1_1") (pintype "passive"))
      (node (ref "TP64") (pin "1") (pintype "passive"))
      (node (ref "TP65") (pin "1") (pintype "passive"))
      (node (ref "U1") (pin "15") (pinfunction "PVDD_15") (pintype "power_in"))
      (node (ref "U1") (pin "7") (pinfunction "AVDD_7") (pintype "power_in"))
    )
  )
)
